# NTC.net
KiCad netlist of a schematic drawn in Altium Designer
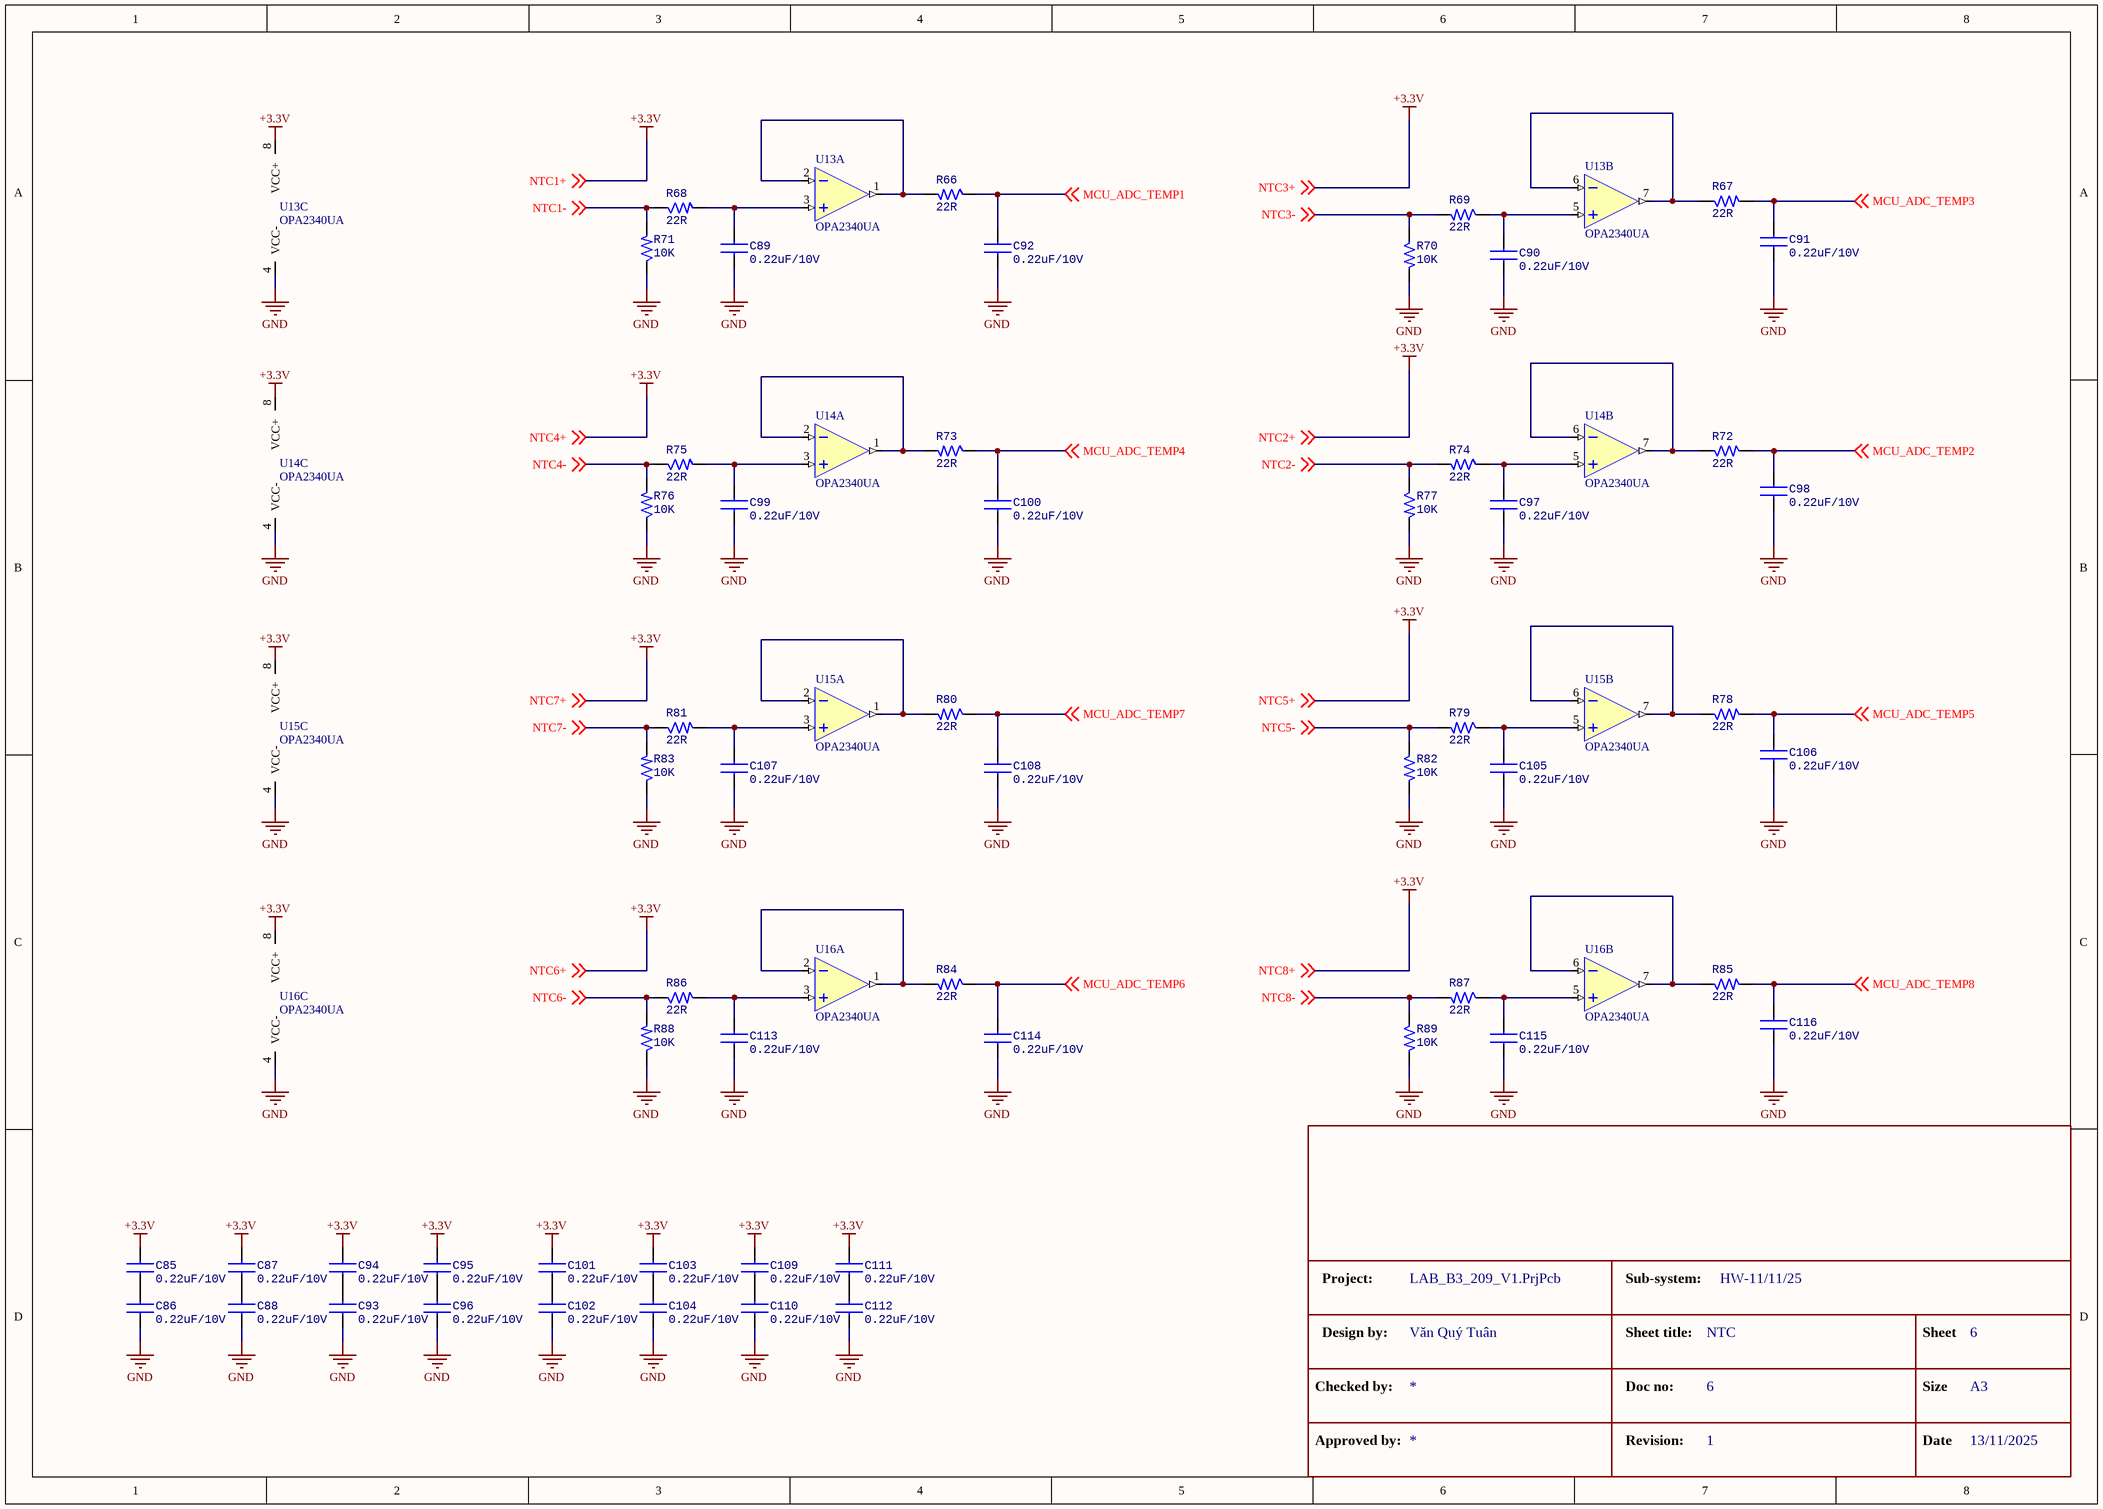
[diagram p0: NTC.SchDoc]

(export (version "E")
  (design (tool "Eeschema 10.0.6"))
  (components
    (comp (ref "C85") (value "0.22uF/10V") (footprint "CAP-CER-0603") (libsource (lib "ID") (part "CAP-CER")))
    (comp (ref "C86") (value "0.22uF/10V") (footprint "CAP-CER-0603") (libsource (lib "ID") (part "CAP-CER")))
    (comp (ref "C87") (value "0.22uF/10V") (footprint "CAP-CER-0603") (libsource (lib "ID") (part "CAP-CER")))
    (comp (ref "C88") (value "0.22uF/10V") (footprint "CAP-CER-0603") (libsource (lib "ID") (part "CAP-CER")))
    (comp (ref "C89") (value "0.22uF/10V") (footprint "CAP-CER-0603") (libsource (lib "ID") (part "CAP-CER")))
    (comp (ref "C90") (value "0.22uF/10V") (footprint "CAP-CER-0603") (libsource (lib "ID") (part "CAP-CER")))
    (comp (ref "C91") (value "0.22uF/10V") (footprint "CAP-CER-0603") (libsource (lib "ID") (part "CAP-CER")))
    (comp (ref "C92") (value "0.22uF/10V") (footprint "CAP-CER-0603") (libsource (lib "ID") (part "CAP-CER")))
    (comp (ref "C93") (value "0.22uF/10V") (footprint "CAP-CER-0603") (libsource (lib "ID") (part "CAP-CER")))
    (comp (ref "C94") (value "0.22uF/10V") (footprint "CAP-CER-0603") (libsource (lib "ID") (part "CAP-CER")))
    (comp (ref "C95") (value "0.22uF/10V") (footprint "CAP-CER-0603") (libsource (lib "ID") (part "CAP-CER")))
    (comp (ref "C96") (value "0.22uF/10V") (footprint "CAP-CER-0603") (libsource (lib "ID") (part "CAP-CER")))
    (comp (ref "C97") (value "0.22uF/10V") (footprint "CAP-CER-0603") (libsource (lib "ID") (part "CAP-CER")))
    (comp (ref "C98") (value "0.22uF/10V") (footprint "CAP-CER-0603") (libsource (lib "ID") (part "CAP-CER")))
    (comp (ref "C99") (value "0.22uF/10V") (footprint "CAP-CER-0603") (libsource (lib "ID") (part "CAP-CER")))
    (comp (ref "C100")
      (value "0.22uF/10V")
      (footprint "CAP-CER-0603")
      (libsource (lib "ID") (part "CAP-CER"))
    )
    (comp (ref "C101")
      (value "0.22uF/10V")
      (footprint "CAP-CER-0603")
      (libsource (lib "ID") (part "CAP-CER"))
    )
    (comp (ref "C102")
      (value "0.22uF/10V")
      (footprint "CAP-CER-0603")
      (libsource (lib "ID") (part "CAP-CER"))
    )
    (comp (ref "C103")
      (value "0.22uF/10V")
      (footprint "CAP-CER-0603")
      (libsource (lib "ID") (part "CAP-CER"))
    )
    (comp (ref "C104")
      (value "0.22uF/10V")
      (footprint "CAP-CER-0603")
      (libsource (lib "ID") (part "CAP-CER"))
    )
    (comp (ref "C105")
      (value "0.22uF/10V")
      (footprint "CAP-CER-0603")
      (libsource (lib "ID") (part "CAP-CER"))
    )
    (comp (ref "C106")
      (value "0.22uF/10V")
      (footprint "CAP-CER-0603")
      (libsource (lib "ID") (part "CAP-CER"))
    )
    (comp (ref "C107")
      (value "0.22uF/10V")
      (footprint "CAP-CER-0603")
      (libsource (lib "ID") (part "CAP-CER"))
    )
    (comp (ref "C108")
      (value "0.22uF/10V")
      (footprint "CAP-CER-0603")
      (libsource (lib "ID") (part "CAP-CER"))
    )
    (comp (ref "C109")
      (value "0.22uF/10V")
      (footprint "CAP-CER-0603")
      (libsource (lib "ID") (part "CAP-CER"))
    )
    (comp (ref "C110")
      (value "0.22uF/10V")
      (footprint "CAP-CER-0603")
      (libsource (lib "ID") (part "CAP-CER"))
    )
    (comp (ref "C111")
      (value "0.22uF/10V")
      (footprint "CAP-CER-0603")
      (libsource (lib "ID") (part "CAP-CER"))
    )
    (comp (ref "C112")
      (value "0.22uF/10V")
      (footprint "CAP-CER-0603")
      (libsource (lib "ID") (part "CAP-CER"))
    )
    (comp (ref "C113")
      (value "0.22uF/10V")
      (footprint "CAP-CER-0603")
      (libsource (lib "ID") (part "CAP-CER"))
    )
    (comp (ref "C114")
      (value "0.22uF/10V")
      (footprint "CAP-CER-0603")
      (libsource (lib "ID") (part "CAP-CER"))
    )
    (comp (ref "C115")
      (value "0.22uF/10V")
      (footprint "CAP-CER-0603")
      (libsource (lib "ID") (part "CAP-CER"))
    )
    (comp (ref "C116")
      (value "0.22uF/10V")
      (footprint "CAP-CER-0603")
      (libsource (lib "ID") (part "CAP-CER"))
    )
    (comp (ref "R66") (value "22R") (footprint "RES-SMD-0603") (libsource (lib "ID") (part "RES-SMD")))
    (comp (ref "R67") (value "22R") (footprint "RES-SMD-0603") (libsource (lib "ID") (part "RES-SMD")))
    (comp (ref "R68") (value "22R") (footprint "RES-SMD-0603") (libsource (lib "ID") (part "RES-SMD")))
    (comp (ref "R69") (value "22R") (footprint "RES-SMD-0603") (libsource (lib "ID") (part "RES-SMD")))
    (comp (ref "R70") (value "10K") (footprint "RES-SMD-0603") (libsource (lib "ID") (part "RES-SMD")))
    (comp (ref "R71") (value "10K") (footprint "RES-SMD-0603") (libsource (lib "ID") (part "RES-SMD")))
    (comp (ref "R72") (value "22R") (footprint "RES-SMD-0603") (libsource (lib "ID") (part "RES-SMD")))
    (comp (ref "R73") (value "22R") (footprint "RES-SMD-0603") (libsource (lib "ID") (part "RES-SMD")))
    (comp (ref "R74") (value "22R") (footprint "RES-SMD-0603") (libsource (lib "ID") (part "RES-SMD")))
    (comp (ref "R75") (value "22R") (footprint "RES-SMD-0603") (libsource (lib "ID") (part "RES-SMD")))
    (comp (ref "R76") (value "10K") (footprint "RES-SMD-0603") (libsource (lib "ID") (part "RES-SMD")))
    (comp (ref "R77") (value "10K") (footprint "RES-SMD-0603") (libsource (lib "ID") (part "RES-SMD")))
    (comp (ref "R78") (value "22R") (footprint "RES-SMD-0603") (libsource (lib "ID") (part "RES-SMD")))
    (comp (ref "R79") (value "22R") (footprint "RES-SMD-0603") (libsource (lib "ID") (part "RES-SMD")))
    (comp (ref "R80") (value "22R") (footprint "RES-SMD-0603") (libsource (lib "ID") (part "RES-SMD")))
    (comp (ref "R81") (value "22R") (footprint "RES-SMD-0603") (libsource (lib "ID") (part "RES-SMD")))
    (comp (ref "R82") (value "10K") (footprint "RES-SMD-0603") (libsource (lib "ID") (part "RES-SMD")))
    (comp (ref "R83") (value "10K") (footprint "RES-SMD-0603") (libsource (lib "ID") (part "RES-SMD")))
    (comp (ref "R84") (value "22R") (footprint "RES-SMD-0603") (libsource (lib "ID") (part "RES-SMD")))
    (comp (ref "R85") (value "22R") (footprint "RES-SMD-0603") (libsource (lib "ID") (part "RES-SMD")))
    (comp (ref "R86") (value "22R") (footprint "RES-SMD-0603") (libsource (lib "ID") (part "RES-SMD")))
    (comp (ref "R87") (value "22R") (footprint "RES-SMD-0603") (libsource (lib "ID") (part "RES-SMD")))
    (comp (ref "R88") (value "10K") (footprint "RES-SMD-0603") (libsource (lib "ID") (part "RES-SMD")))
    (comp (ref "R89") (value "10K") (footprint "RES-SMD-0603") (libsource (lib "ID") (part "RES-SMD")))
    (comp (ref "U13")
      (value "OPA2340UA")
      (footprint "SOIC-8")
      (description "Dual JFET Low-Noise Operational Amplifiers")
      (fields
        (field (name "MANUFACTURER") "STMicroelectronics")
        (field (name "MANUFACTURER PART NUMBER") "TL072CDT")
      )
      (libsource (lib "Schematic-Lib-PhilsLab") (part "TL072CDT"))
    )
    (comp (ref "U14")
      (value "OPA2340UA")
      (footprint "SOIC-8")
      (description "Dual JFET Low-Noise Operational Amplifiers")
      (fields
        (field (name "MANUFACTURER") "STMicroelectronics")
        (field (name "MANUFACTURER PART NUMBER") "TL072CDT")
      )
      (libsource (lib "Schematic-Lib-PhilsLab") (part "TL072CDT"))
    )
    (comp (ref "U15")
      (value "OPA2340UA")
      (footprint "SOIC-8")
      (description "Dual JFET Low-Noise Operational Amplifiers")
      (fields
        (field (name "MANUFACTURER") "STMicroelectronics")
        (field (name "MANUFACTURER PART NUMBER") "TL072CDT")
      )
      (libsource (lib "Schematic-Lib-PhilsLab") (part "TL072CDT"))
    )
    (comp (ref "U16")
      (value "OPA2340UA")
      (footprint "SOIC-8")
      (description "Dual JFET Low-Noise Operational Amplifiers")
      (fields
        (field (name "MANUFACTURER") "STMicroelectronics")
        (field (name "MANUFACTURER PART NUMBER") "TL072CDT")
      )
      (libsource (lib "Schematic-Lib-PhilsLab") (part "TL072CDT"))
    )
  )
  (nets
    (net (code "1") (name "+3.3V") (class "Default")
      (node (ref "C101") (pin "1") (pinfunction "1_1") (pintype "passive"))
      (node (ref "C103") (pin "1") (pinfunction "1_1") (pintype "passive"))
      (node (ref "C109") (pin "1") (pinfunction "1_1") (pintype "passive"))
      (node (ref "C111") (pin "1") (pinfunction "1_1") (pintype "passive"))
      (node (ref "C85") (pin "1") (pinfunction "1_1") (pintype "passive"))
      (node (ref "C87") (pin "1") (pinfunction "1_1") (pintype "passive"))
      (node (ref "C94") (pin "1") (pinfunction "1_1") (pintype "passive"))
      (node (ref "C95") (pin "1") (pinfunction "1_1") (pintype "passive"))
      (node (ref "U13") (pin "8") (pinfunction "VCC+_8") (pintype "passive"))
      (node (ref "U14") (pin "8") (pinfunction "VCC+_8") (pintype "passive"))
      (node (ref "U15") (pin "8") (pinfunction "VCC+_8") (pintype "passive"))
      (node (ref "U16") (pin "8") (pinfunction "VCC+_8") (pintype "passive"))
    )
    (net (code "2") (name "GND") (class "Default")
      (node (ref "C100") (pin "2") (pinfunction "2_2") (pintype "passive"))
      (node (ref "C102") (pin "2") (pinfunction "2_2") (pintype "passive"))
      (node (ref "C104") (pin "2") (pinfunction "2_2") (pintype "passive"))
      (node (ref "C105") (pin "2") (pinfunction "2_2") (pintype "passive"))
      (node (ref "C106") (pin "2") (pinfunction "2_2") (pintype "passive"))
      (node (ref "C107") (pin "2") (pinfunction "2_2") (pintype "passive"))
      (node (ref "C108") (pin "2") (pinfunction "2_2") (pintype "passive"))
      (node (ref "C110") (pin "2") (pinfunction "2_2") (pintype "passive"))
      (node (ref "C112") (pin "2") (pinfunction "2_2") (pintype "passive"))
      (node (ref "C113") (pin "2") (pinfunction "2_2") (pintype "passive"))
      (node (ref "C114") (pin "2") (pinfunction "2_2") (pintype "passive"))
      (node (ref "C115") (pin "2") (pinfunction "2_2") (pintype "passive"))
      (node (ref "C116") (pin "2") (pinfunction "2_2") (pintype "passive"))
      (node (ref "C86") (pin "2") (pinfunction "2_2") (pintype "passive"))
      (node (ref "C88") (pin "2") (pinfunction "2_2") (pintype "passive"))
      (node (ref "C89") (pin "2") (pinfunction "2_2") (pintype "passive"))
      (node (ref "C90") (pin "2") (pinfunction "2_2") (pintype "passive"))
      (node (ref "C91") (pin "2") (pinfunction "2_2") (pintype "passive"))
      (node (ref "C92") (pin "2") (pinfunction "2_2") (pintype "passive"))
      (node (ref "C93") (pin "2") (pinfunction "2_2") (pintype "passive"))
      (node (ref "C96") (pin "2") (pinfunction "2_2") (pintype "passive"))
      (node (ref "C97") (pin "2") (pinfunction "2_2") (pintype "passive"))
      (node (ref "C98") (pin "2") (pinfunction "2_2") (pintype "passive"))
      (node (ref "C99") (pin "2") (pinfunction "2_2") (pintype "passive"))
      (node (ref "R70") (pin "2") (pinfunction "2_2") (pintype "passive"))
      (node (ref "R71") (pin "1") (pinfunction "1_1") (pintype "passive"))
      (node (ref "R76") (pin "1") (pinfunction "1_1") (pintype "passive"))
      (node (ref "R77") (pin "2") (pinfunction "2_2") (pintype "passive"))
      (node (ref "R82") (pin "2") (pinfunction "2_2") (pintype "passive"))
      (node (ref "R83") (pin "1") (pinfunction "1_1") (pintype "passive"))
      (node (ref "R88") (pin "1") (pinfunction "1_1") (pintype "passive"))
      (node (ref "R89") (pin "2") (pinfunction "2_2") (pintype "passive"))
      (node (ref "U13") (pin "4") (pinfunction "VCC-_4") (pintype "passive"))
      (node (ref "U14") (pin "4") (pinfunction "VCC-_4") (pintype "passive"))
      (node (ref "U15") (pin "4") (pinfunction "VCC-_4") (pintype "passive"))
      (node (ref "U16") (pin "4") (pinfunction "VCC-_4") (pintype "passive"))
    )
    (net (code "3") (name "MCU_ADC_TEMP1") (class "Default")
      (node (ref "C92") (pin "1") (pinfunction "1_1") (pintype "passive"))
      (node (ref "R66") (pin "1") (pinfunction "1_1") (pintype "passive"))
    )
    (net (code "4") (name "MCU_ADC_TEMP2") (class "Default")
      (node (ref "C98") (pin "1") (pinfunction "1_1") (pintype "passive"))
      (node (ref "R72") (pin "2") (pinfunction "2_2") (pintype "passive"))
    )
    (net (code "5") (name "MCU_ADC_TEMP3") (class "Default")
      (node (ref "C91") (pin "1") (pinfunction "1_1") (pintype "passive"))
      (node (ref "R67") (pin "2") (pinfunction "2_2") (pintype "passive"))
    )
    (net (code "6") (name "MCU_ADC_TEMP4") (class "Default")
      (node (ref "C100") (pin "1") (pinfunction "1_1") (pintype "passive"))
      (node (ref "R73") (pin "1") (pinfunction "1_1") (pintype "passive"))
    )
    (net (code "7") (name "MCU_ADC_TEMP5") (class "Default")
      (node (ref "C106") (pin "1") (pinfunction "1_1") (pintype "passive"))
      (node (ref "R78") (pin "2") (pinfunction "2_2") (pintype "passive"))
    )
    (net (code "8") (name "MCU_ADC_TEMP6") (class "Default")
      (node (ref "C114") (pin "1") (pinfunction "1_1") (pintype "passive"))
      (node (ref "R84") (pin "1") (pinfunction "1_1") (pintype "passive"))
    )
    (net (code "9") (name "MCU_ADC_TEMP7") (class "Default")
      (node (ref "C108") (pin "1") (pinfunction "1_1") (pintype "passive"))
      (node (ref "R80") (pin "1") (pinfunction "1_1") (pintype "passive"))
    )
    (net (code "10") (name "MCU_ADC_TEMP8") (class "Default")
      (node (ref "C116") (pin "1") (pinfunction "1_1") (pintype "passive"))
      (node (ref "R85") (pin "2") (pinfunction "2_2") (pintype "passive"))
    )
    (net (code "11") (name "NTC1-") (class "Default")
      (node (ref "R68") (pin "1") (pinfunction "1_1") (pintype "passive"))
      (node (ref "R71") (pin "2") (pinfunction "2_2") (pintype "passive"))
    )
    (net (code "12") (name "NTC2-") (class "Default")
      (node (ref "R74") (pin "2") (pinfunction "2_2") (pintype "passive"))
      (node (ref "R77") (pin "1") (pinfunction "1_1") (pintype "passive"))
    )
    (net (code "13") (name "NTC3-") (class "Default")
      (node (ref "R69") (pin "2") (pinfunction "2_2") (pintype "passive"))
      (node (ref "R70") (pin "1") (pinfunction "1_1") (pintype "passive"))
    )
    (net (code "14") (name "NTC4-") (class "Default")
      (node (ref "R75") (pin "1") (pinfunction "1_1") (pintype "passive"))
      (node (ref "R76") (pin "2") (pinfunction "2_2") (pintype "passive"))
    )
    (net (code "15") (name "NTC5-") (class "Default")
      (node (ref "R79") (pin "2") (pinfunction "2_2") (pintype "passive"))
      (node (ref "R82") (pin "1") (pinfunction "1_1") (pintype "passive"))
    )
    (net (code "16") (name "NTC6-") (class "Default")
      (node (ref "R86") (pin "1") (pinfunction "1_1") (pintype "passive"))
      (node (ref "R88") (pin "2") (pinfunction "2_2") (pintype "passive"))
    )
    (net (code "17") (name "NTC7-") (class "Default")
      (node (ref "R81") (pin "1") (pinfunction "1_1") (pintype "passive"))
      (node (ref "R83") (pin "2") (pinfunction "2_2") (pintype "passive"))
    )
    (net (code "18") (name "NTC8-") (class "Default")
      (node (ref "R87") (pin "2") (pinfunction "2_2") (pintype "passive"))
      (node (ref "R89") (pin "1") (pinfunction "1_1") (pintype "passive"))
    )
    (net (code "19") (name "Net-(C85-Pad2)") (class "Default")
      (node (ref "C85") (pin "2") (pinfunction "2_2") (pintype "passive"))
      (node (ref "C86") (pin "1") (pinfunction "1_1") (pintype "passive"))
    )
    (net (code "20") (name "Net-(C87-Pad2)") (class "Default")
      (node (ref "C87") (pin "2") (pinfunction "2_2") (pintype "passive"))
      (node (ref "C88") (pin "1") (pinfunction "1_1") (pintype "passive"))
    )
    (net (code "21") (name "Net-(C93-Pad1)") (class "Default")
      (node (ref "C93") (pin "1") (pinfunction "1_1") (pintype "passive"))
      (node (ref "C94") (pin "2") (pinfunction "2_2") (pintype "passive"))
    )
    (net (code "22") (name "Net-(C95-Pad2)") (class "Default")
      (node (ref "C95") (pin "2") (pinfunction "2_2") (pintype "passive"))
      (node (ref "C96") (pin "1") (pinfunction "1_1") (pintype "passive"))
    )
    (net (code "23") (name "Net-(C101-Pad2)") (class "Default")
      (node (ref "C101") (pin "2") (pinfunction "2_2") (pintype "passive"))
      (node (ref "C102") (pin "1") (pinfunction "1_1") (pintype "passive"))
    )
    (net (code "24") (name "Net-(C103-Pad2)") (class "Default")
      (node (ref "C103") (pin "2") (pinfunction "2_2") (pintype "passive"))
      (node (ref "C104") (pin "1") (pinfunction "1_1") (pintype "passive"))
    )
    (net (code "25") (name "Net-(C109-Pad2)") (class "Default")
      (node (ref "C109") (pin "2") (pinfunction "2_2") (pintype "passive"))
      (node (ref "C110") (pin "1") (pinfunction "1_1") (pintype "passive"))
    )
    (net (code "26") (name "Net-(C111-Pad2)") (class "Default")
      (node (ref "C111") (pin "2") (pinfunction "2_2") (pintype "passive"))
      (node (ref "C112") (pin "1") (pinfunction "1_1") (pintype "passive"))
    )
    (net (code "27") (name "Net-(U13A-1IN+)") (class "Default")
      (node (ref "C89") (pin "1") (pinfunction "1_1") (pintype "passive"))
      (node (ref "R68") (pin "2") (pinfunction "2_2") (pintype "passive"))
      (node (ref "U13") (pin "3") (pinfunction "1IN+_3") (pintype "input"))
    )
    (net (code "28") (name "Net-(U13A-1IN-)") (class "Default")
      (node (ref "R66") (pin "2") (pinfunction "2_2") (pintype "passive"))
      (node (ref "U13") (pin "1") (pinfunction "1OUT_1") (pintype "output"))
      (node (ref "U13") (pin "2") (pinfunction "1IN-_2") (pintype "input"))
    )
    (net (code "29") (name "Net-(U13B-2IN+)") (class "Default")
      (node (ref "C90") (pin "1") (pinfunction "1_1") (pintype "passive"))
      (node (ref "R69") (pin "1") (pinfunction "1_1") (pintype "passive"))
      (node (ref "U13") (pin "5") (pinfunction "2IN+_5") (pintype "input"))
    )
    (net (code "30") (name "Net-(U13B-2IN-)") (class "Default")
      (node (ref "R67") (pin "1") (pinfunction "1_1") (pintype "passive"))
      (node (ref "U13") (pin "6") (pinfunction "2IN-_6") (pintype "input"))
      (node (ref "U13") (pin "7") (pinfunction "2OUT_7") (pintype "output"))
    )
    (net (code "31") (name "Net-(U14A-1IN+)") (class "Default")
      (node (ref "C99") (pin "1") (pinfunction "1_1") (pintype "passive"))
      (node (ref "R75") (pin "2") (pinfunction "2_2") (pintype "passive"))
      (node (ref "U14") (pin "3") (pinfunction "1IN+_3") (pintype "input"))
    )
    (net (code "32") (name "Net-(U14A-1IN-)") (class "Default")
      (node (ref "R73") (pin "2") (pinfunction "2_2") (pintype "passive"))
      (node (ref "U14") (pin "1") (pinfunction "1OUT_1") (pintype "output"))
      (node (ref "U14") (pin "2") (pinfunction "1IN-_2") (pintype "input"))
    )
    (net (code "33") (name "Net-(U14B-2IN+)") (class "Default")
      (node (ref "C97") (pin "1") (pinfunction "1_1") (pintype "passive"))
      (node (ref "R74") (pin "1") (pinfunction "1_1") (pintype "passive"))
      (node (ref "U14") (pin "5") (pinfunction "2IN+_5") (pintype "input"))
    )
    (net (code "34") (name "Net-(U14B-2IN-)") (class "Default")
      (node (ref "R72") (pin "1") (pinfunction "1_1") (pintype "passive"))
      (node (ref "U14") (pin "6") (pinfunction "2IN-_6") (pintype "input"))
      (node (ref "U14") (pin "7") (pinfunction "2OUT_7") (pintype "output"))
    )
    (net (code "35") (name "Net-(U15A-1IN+)") (class "Default")
      (node (ref "C107") (pin "1") (pinfunction "1_1") (pintype "passive"))
      (node (ref "R81") (pin "2") (pinfunction "2_2") (pintype "passive"))
      (node (ref "U15") (pin "3") (pinfunction "1IN+_3") (pintype "input"))
    )
    (net (code "36") (name "Net-(U15A-1IN-)") (class "Default")
      (node (ref "R80") (pin "2") (pinfunction "2_2") (pintype "passive"))
      (node (ref "U15") (pin "1") (pinfunction "1OUT_1") (pintype "output"))
      (node (ref "U15") (pin "2") (pinfunction "1IN-_2") (pintype "input"))
    )
    (net (code "37") (name "Net-(U15B-2IN+)") (class "Default")
      (node (ref "C105") (pin "1") (pinfunction "1_1") (pintype "passive"))
      (node (ref "R79") (pin "1") (pinfunction "1_1") (pintype "passive"))
      (node (ref "U15") (pin "5") (pinfunction "2IN+_5") (pintype "input"))
    )
    (net (code "38") (name "Net-(U15B-2IN-)") (class "Default")
      (node (ref "R78") (pin "1") (pinfunction "1_1") (pintype "passive"))
      (node (ref "U15") (pin "6") (pinfunction "2IN-_6") (pintype "input"))
      (node (ref "U15") (pin "7") (pinfunction "2OUT_7") (pintype "output"))
    )
    (net (code "39") (name "Net-(U16A-1IN+)") (class "Default")
      (node (ref "C113") (pin "1") (pinfunction "1_1") (pintype "passive"))
      (node (ref "R86") (pin "2") (pinfunction "2_2") (pintype "passive"))
      (node (ref "U16") (pin "3") (pinfunction "1IN+_3") (pintype "input"))
    )
    (net (code "40") (name "Net-(U16A-1IN-)") (class "Default")
      (node (ref "R84") (pin "2") (pinfunction "2_2") (pintype "passive"))
      (node (ref "U16") (pin "1") (pinfunction "1OUT_1") (pintype "output"))
      (node (ref "U16") (pin "2") (pinfunction "1IN-_2") (pintype "input"))
    )
    (net (code "41") (name "Net-(U16B-2IN+)") (class "Default")
      (node (ref "C115") (pin "1") (pinfunction "1_1") (pintype "passive"))
      (node (ref "R87") (pin "1") (pinfunction "1_1") (pintype "passive"))
      (node (ref "U16") (pin "5") (pinfunction "2IN+_5") (pintype "input"))
    )
    (net (code "42") (name "Net-(U16B-2IN-)") (class "Default")
      (node (ref "R85") (pin "1") (pinfunction "1_1") (pintype "passive"))
      (node (ref "U16") (pin "6") (pinfunction "2IN-_6") (pintype "input"))
      (node (ref "U16") (pin "7") (pinfunction "2OUT_7") (pintype "output"))
    )
  )
)
